# AQCA-Light-Control-CoolWhite-A0.net
KiCad netlist of a schematic drawn in Altium Designer
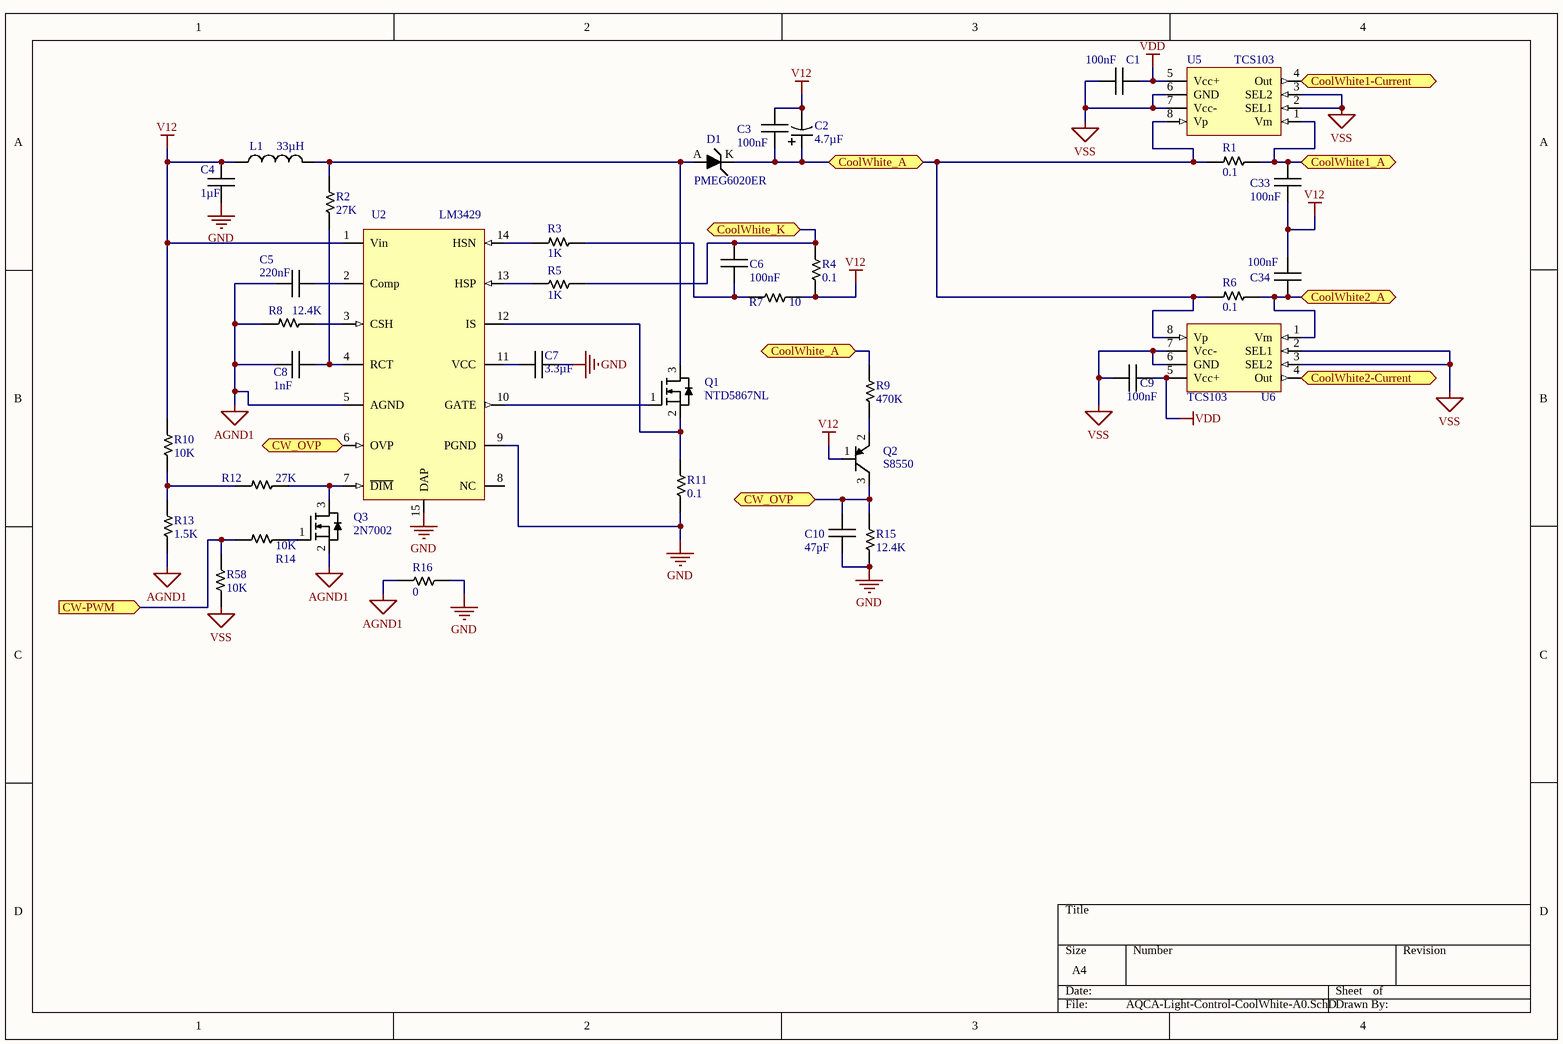
[diagram p0: AQCA-Light-Control-CoolWhite-A0.SchDoc]

(export (version "E")
  (design (tool "Eeschema 10.0.6"))
  (components
    (comp (ref "C1")
      (value "100nF")
      (footprint "CAPC1608N")
      (fields (field (name "VOLTAGE") "16V"))
      (libsource (lib "Megaxone") (part "Capacitor"))
    )
    (comp (ref "C2")
      (value "4.7µF")
      (footprint "CAPPR2-5x11")
      (fields (field (name "VOLTAGE") "100V"))
      (libsource (lib "Megaxone") (part "Capacitor Polarised"))
    )
    (comp (ref "C3")
      (value "100nF")
      (footprint "CAPC2012N")
      (fields (field (name "VOLTAGE") "100V"))
      (libsource (lib "Megaxone") (part "Capacitor"))
    )
    (comp (ref "C4")
      (value "1µF")
      (footprint "CAPC1608N")
      (fields (field (name "VOLTAGE") "25V"))
      (libsource (lib "Megaxone") (part "Capacitor"))
    )
    (comp (ref "C5")
      (value "220nF")
      (footprint "CAPC1608N")
      (fields (field (name "VOLTAGE") "25V"))
      (libsource (lib "Megaxone") (part "Capacitor"))
    )
    (comp (ref "C6")
      (value "100nF")
      (footprint "CAPC1608N")
      (fields (field (name "VOLTAGE") "16V"))
      (libsource (lib "Megaxone") (part "Capacitor"))
    )
    (comp (ref "C7")
      (value "3.3µF")
      (footprint "CAPC1608N")
      (fields (field (name "VOLTAGE") "16V"))
      (libsource (lib "Megaxone") (part "Capacitor"))
    )
    (comp (ref "C8")
      (value "1nF")
      (footprint "CAPC1608N")
      (fields (field (name "VOLTAGE") "50V"))
      (libsource (lib "Megaxone") (part "Capacitor"))
    )
    (comp (ref "C9")
      (value "100nF")
      (footprint "CAPC1608N")
      (fields (field (name "VOLTAGE") "16V"))
      (libsource (lib "Megaxone") (part "Capacitor"))
    )
    (comp (ref "C10")
      (value "47pF")
      (footprint "CAPC1608N")
      (fields (field (name "VOLTAGE") "100V"))
      (libsource (lib "Megaxone") (part "Capacitor"))
    )
    (comp (ref "C33")
      (value "100nF")
      (footprint "CAPC2012N")
      (fields (field (name "VOLTAGE") "100V"))
      (libsource (lib "Megaxone") (part "Capacitor"))
    )
    (comp (ref "C34")
      (value "100nF")
      (footprint "CAPC2012N")
      (fields (field (name "VOLTAGE") "100V"))
      (libsource (lib "Megaxone") (part "Capacitor"))
    )
    (comp (ref "D1")
      (value "PMEG6020ER")
      (footprint "SOD123")
      (libsource (lib "Megaxone") (part "Schottky Diode"))
    )
    (comp (ref "L1")
      (value "33µH")
      (footprint "Inductor AIUR5-6")
      (libsource (lib "Megaxone") (part "Inductor"))
    )
    (comp (ref "Q1")
      (value "NTD5867NL")
      (footprint "DPAK 369AA")
      (libsource (lib "Megaxone") (part "MOSFET N-Ch"))
    )
    (comp (ref "Q2") (value "S8550") (footprint "SOT23_N") (libsource (lib "Megaxone") (part "PNP")))
    (comp (ref "Q3")
      (value "2N7002")
      (footprint "SOT23-3N")
      (libsource (lib "Megaxone") (part "MOSFET N-Ch"))
    )
    (comp (ref "R1") (value "0.1") (footprint "RESC2012N") (libsource (lib "") (part "Resistor_2")))
    (comp (ref "R2") (value "27K") (footprint "RESC1608N") (libsource (lib "") (part "Resistor_1")))
    (comp (ref "R3") (value "1K") (footprint "RESC1608N") (libsource (lib "") (part "Resistor_2")))
    (comp (ref "R4") (value "0.1") (footprint "RESC2012N") (libsource (lib "") (part "Resistor_1")))
    (comp (ref "R5") (value "1K") (footprint "RESC1608N") (libsource (lib "Megaxone") (part "Resistor")))
    (comp (ref "R6") (value "0.1") (footprint "RESC2012N") (libsource (lib "") (part "Resistor_2")))
    (comp (ref "R7") (value "10") (footprint "RESC1608N") (libsource (lib "Megaxone") (part "Resistor")))
    (comp (ref "R8") (value "12.4K") (footprint "RESC1608N") (libsource (lib "") (part "Resistor_2")))
    (comp (ref "R9") (value "470K") (footprint "RESC1608N") (libsource (lib "") (part "Resistor_1")))
    (comp (ref "R10") (value "10K") (footprint "RESC1608N") (libsource (lib "") (part "Resistor_1")))
    (comp (ref "R11") (value "0.1") (footprint "RESC6332N") (libsource (lib "") (part "Resistor_1")))
    (comp (ref "R12") (value "27K") (footprint "RESC1608N") (libsource (lib "") (part "Resistor_2")))
    (comp (ref "R13") (value "1.5K") (footprint "RESC1608N") (libsource (lib "") (part "Resistor_1")))
    (comp (ref "R14") (value "10K") (footprint "RESC1608N") (libsource (lib "") (part "Resistor_2")))
    (comp (ref "R15") (value "12.4K") (footprint "RESC1608N") (libsource (lib "") (part "Resistor_1")))
    (comp (ref "R16") (value "0") (footprint "RESC1608N") (libsource (lib "Megaxone") (part "Resistor")))
    (comp (ref "R58") (value "10K") (footprint "RESC1608N") (libsource (lib "") (part "Resistor_3")))
    (comp (ref "U2")
      (value "LM3429")
      (footprint "TSOP65P640_HS-14N")
      (libsource (lib "Megaxone") (part "LM3429"))
    )
    (comp (ref "U5") (value "TCS103") (footprint "TSSOP8N_N") (libsource (lib "") (part "TCS103_1")))
    (comp (ref "U6") (value "TCS103") (footprint "TSSOP8N_N") (libsource (lib "Megaxone") (part "TCS103")))
  )
  (nets
    (net (code "1") (name "/CW-PWM") (class "Default")
      (node (ref "R14") (pin "2") (pinfunction "2_2") (pintype "passive"))
      (node (ref "R58") (pin "1") (pinfunction "1_1") (pintype "passive"))
    )
    (net (code "2") (name "/CW_OVP") (class "Default")
      (node (ref "C10") (pin "2") (pinfunction "2_2") (pintype "passive"))
      (node (ref "Q2") (pin "3") (pinfunction "C_3") (pintype "passive"))
      (node (ref "R15") (pin "2") (pinfunction "2_2") (pintype "passive"))
      (node (ref "U2") (pin "6") (pinfunction "OVP_6") (pintype "input"))
    )
    (net (code "3") (name "/CoolWhite1-Current") (class "Default")
      (node (ref "U5") (pin "4") (pinfunction "Out_4") (pintype "output"))
    )
    (net (code "4") (name "/CoolWhite1_A") (class "Default")
      (node (ref "C33") (pin "2") (pinfunction "2_2") (pintype "passive"))
      (node (ref "R1") (pin "1") (pinfunction "1_1") (pintype "passive"))
      (node (ref "U5") (pin "1") (pinfunction "Vm_1") (pintype "input"))
    )
    (net (code "5") (name "/CoolWhite2-Current") (class "Default")
      (node (ref "U6") (pin "4") (pinfunction "Out_4") (pintype "output"))
    )
    (net (code "6") (name "/CoolWhite2_A") (class "Default")
      (node (ref "C34") (pin "1") (pinfunction "1_1") (pintype "passive"))
      (node (ref "R6") (pin "1") (pinfunction "1_1") (pintype "passive"))
      (node (ref "U6") (pin "1") (pinfunction "Vm_1") (pintype "input"))
    )
    (net (code "7") (name "/CoolWhite_A") (class "Default")
      (node (ref "C2") (pin "1") (pinfunction "1_1") (pintype "passive"))
      (node (ref "C3") (pin "1") (pinfunction "1_1") (pintype "passive"))
      (node (ref "D1") (pin "K") (pinfunction "Kathode_K") (pintype "power_in"))
      (node (ref "R1") (pin "2") (pinfunction "2_2") (pintype "passive"))
      (node (ref "R6") (pin "2") (pinfunction "2_2") (pintype "passive"))
      (node (ref "R9") (pin "2") (pinfunction "2_2") (pintype "passive"))
      (node (ref "U5") (pin "8") (pinfunction "Vp_8") (pintype "input"))
      (node (ref "U6") (pin "8") (pinfunction "Vp_8") (pintype "input"))
    )
    (net (code "8") (name "/CoolWhite_K") (class "Default")
      (node (ref "C6") (pin "2") (pinfunction "2_2") (pintype "passive"))
      (node (ref "R4") (pin "2") (pinfunction "2_2") (pintype "passive"))
      (node (ref "R5") (pin "2") (pinfunction "2_2") (pintype "passive"))
    )
    (net (code "9") (name "AGND1") (class "Default")
      (node (ref "C5") (pin "1") (pinfunction "1_1") (pintype "passive"))
      (node (ref "C8") (pin "1") (pinfunction "1_1") (pintype "passive"))
      (node (ref "Q3") (pin "2") (pinfunction "S_2") (pintype "passive"))
      (node (ref "R13") (pin "1") (pinfunction "1_1") (pintype "passive"))
      (node (ref "R16") (pin "1") (pinfunction "1_1") (pintype "passive"))
      (node (ref "R8") (pin "2") (pinfunction "2_2") (pintype "passive"))
      (node (ref "U2") (pin "5") (pinfunction "AGND_5") (pintype "power_in"))
    )
    (net (code "10") (name "GND") (class "Default")
      (node (ref "C10") (pin "1") (pinfunction "1_1") (pintype "passive"))
      (node (ref "C4") (pin "1") (pinfunction "1_1") (pintype "passive"))
      (node (ref "C7") (pin "1") (pinfunction "1_1") (pintype "passive"))
      (node (ref "R11") (pin "1") (pinfunction "1_1") (pintype "passive"))
      (node (ref "R15") (pin "1") (pinfunction "1_1") (pintype "passive"))
      (node (ref "R16") (pin "2") (pinfunction "2_2") (pintype "passive"))
      (node (ref "U2") (pin "15") (pinfunction "DAP_15") (pintype "passive"))
      (node (ref "U2") (pin "9") (pinfunction "PGND_9") (pintype "power_in"))
    )
    (net (code "11") (name "Net-(C6-Pad1)") (class "Default")
      (node (ref "C6") (pin "1") (pinfunction "1_1") (pintype "passive"))
      (node (ref "R3") (pin "1") (pinfunction "1_1") (pintype "passive"))
      (node (ref "R7") (pin "1") (pinfunction "1_1") (pintype "passive"))
    )
    (net (code "12") (name "Net-(D1-Anode)") (class "Default")
      (node (ref "D1") (pin "A") (pinfunction "Anode_A") (pintype "power_in"))
      (node (ref "L1") (pin "2") (pinfunction "2_2") (pintype "passive"))
      (node (ref "Q1") (pin "3") (pinfunction "D_3") (pintype "passive"))
      (node (ref "R2") (pin "2") (pinfunction "2_2") (pintype "passive"))
    )
    (net (code "13") (name "Net-(Q1-G)") (class "Default")
      (node (ref "Q1") (pin "1") (pinfunction "G_1") (pintype "passive"))
      (node (ref "U2") (pin "10") (pinfunction "GATE_10") (pintype "output"))
    )
    (net (code "14") (name "Net-(Q1-S)") (class "Default")
      (node (ref "Q1") (pin "2") (pinfunction "S_2") (pintype "passive"))
      (node (ref "R11") (pin "2") (pinfunction "2_2") (pintype "passive"))
      (node (ref "U2") (pin "12") (pinfunction "IS_12") (pintype "passive"))
    )
    (net (code "15") (name "Net-(Q2-E)") (class "Default")
      (node (ref "Q2") (pin "2") (pinfunction "E_2") (pintype "passive"))
      (node (ref "R9") (pin "1") (pinfunction "1_1") (pintype "passive"))
    )
    (net (code "16") (name "Net-(Q3-D)") (class "Default")
      (node (ref "Q3") (pin "3") (pinfunction "D_3") (pintype "passive"))
      (node (ref "R12") (pin "1") (pinfunction "1_1") (pintype "passive"))
      (node (ref "U2") (pin "7") (pinfunction "~{DIM}_7") (pintype "input"))
    )
    (net (code "17") (name "Net-(Q3-G)") (class "Default")
      (node (ref "Q3") (pin "1") (pinfunction "G_1") (pintype "passive"))
      (node (ref "R14") (pin "1") (pinfunction "1_1") (pintype "passive"))
    )
    (net (code "18") (name "Net-(R10-Pad1)") (class "Default")
      (node (ref "R10") (pin "1") (pinfunction "1_1") (pintype "passive"))
      (node (ref "R12") (pin "2") (pinfunction "2_2") (pintype "passive"))
      (node (ref "R13") (pin "2") (pinfunction "2_2") (pintype "passive"))
    )
    (net (code "19") (name "Net-(U2-CSH)") (class "Default")
      (node (ref "R8") (pin "1") (pinfunction "1_1") (pintype "passive"))
      (node (ref "U2") (pin "3") (pinfunction "CSH_3") (pintype "input"))
    )
    (net (code "20") (name "Net-(U2-Comp)") (class "Default")
      (node (ref "C5") (pin "2") (pinfunction "2_2") (pintype "passive"))
      (node (ref "U2") (pin "2") (pinfunction "Comp_2") (pintype "passive"))
    )
    (net (code "21") (name "Net-(U2-HSN)") (class "Default")
      (node (ref "R3") (pin "2") (pinfunction "2_2") (pintype "passive"))
      (node (ref "U2") (pin "14") (pinfunction "HSN_14") (pintype "input"))
    )
    (net (code "22") (name "Net-(U2-HSP)") (class "Default")
      (node (ref "R5") (pin "1") (pinfunction "1_1") (pintype "passive"))
      (node (ref "U2") (pin "13") (pinfunction "HSP_13") (pintype "input"))
    )
    (net (code "23") (name "Net-(U2-RCT)") (class "Default")
      (node (ref "C8") (pin "2") (pinfunction "2_2") (pintype "passive"))
      (node (ref "R2") (pin "1") (pinfunction "1_1") (pintype "passive"))
      (node (ref "U2") (pin "4") (pinfunction "RCT_4") (pintype "passive"))
    )
    (net (code "24") (name "Net-(U2-VCC)") (class "Default")
      (node (ref "C7") (pin "2") (pinfunction "2_2") (pintype "passive"))
      (node (ref "U2") (pin "11") (pinfunction "VCC_11") (pintype "power_in"))
    )
    (net (code "25") (name "V12") (class "Default")
      (node (ref "C2") (pin "2") (pinfunction "2_2") (pintype "passive"))
      (node (ref "C3") (pin "2") (pinfunction "2_2") (pintype "passive"))
      (node (ref "C33") (pin "1") (pinfunction "1_1") (pintype "passive"))
      (node (ref "C34") (pin "2") (pinfunction "2_2") (pintype "passive"))
      (node (ref "C4") (pin "2") (pinfunction "2_2") (pintype "passive"))
      (node (ref "L1") (pin "1") (pinfunction "1_1") (pintype "passive"))
      (node (ref "Q2") (pin "1") (pinfunction "B_1") (pintype "passive"))
      (node (ref "R10") (pin "2") (pinfunction "2_2") (pintype "passive"))
      (node (ref "R4") (pin "1") (pinfunction "1_1") (pintype "passive"))
      (node (ref "R7") (pin "2") (pinfunction "2_2") (pintype "passive"))
      (node (ref "U2") (pin "1") (pinfunction "Vin_1") (pintype "power_in"))
    )
    (net (code "26") (name "VDD") (class "Default")
      (node (ref "C1") (pin "1") (pinfunction "1_1") (pintype "passive"))
      (node (ref "C9") (pin "1") (pinfunction "1_1") (pintype "passive"))
      (node (ref "U5") (pin "5") (pinfunction "Vcc+_5") (pintype "power_in"))
      (node (ref "U6") (pin "5") (pinfunction "Vcc+_5") (pintype "power_in"))
    )
    (net (code "27") (name "VSS") (class "Default")
      (node (ref "C1") (pin "2") (pinfunction "2_2") (pintype "passive"))
      (node (ref "C9") (pin "2") (pinfunction "2_2") (pintype "passive"))
      (node (ref "R58") (pin "2") (pinfunction "2_2") (pintype "passive"))
      (node (ref "U5") (pin "2") (pinfunction "SEL1_2") (pintype "input"))
      (node (ref "U5") (pin "3") (pinfunction "SEL2_3") (pintype "input"))
      (node (ref "U5") (pin "6") (pinfunction "GND_6") (pintype "power_in"))
      (node (ref "U5") (pin "7") (pinfunction "Vcc-_7") (pintype "power_in"))
      (node (ref "U6") (pin "2") (pinfunction "SEL1_2") (pintype "input"))
      (node (ref "U6") (pin "3") (pinfunction "SEL2_3") (pintype "input"))
      (node (ref "U6") (pin "6") (pinfunction "GND_6") (pintype "power_in"))
      (node (ref "U6") (pin "7") (pinfunction "Vcc-_7") (pintype "power_in"))
    )
    (net (code "28") (name "unconnected-(U2-NC-Pad8)") (class "Default")
      (node (ref "U2") (pin "8") (pinfunction "NC_8") (pintype "passive"))
    )
  )
)
